# BTEMS.net
KiCad netlist of a schematic drawn in EAGLE
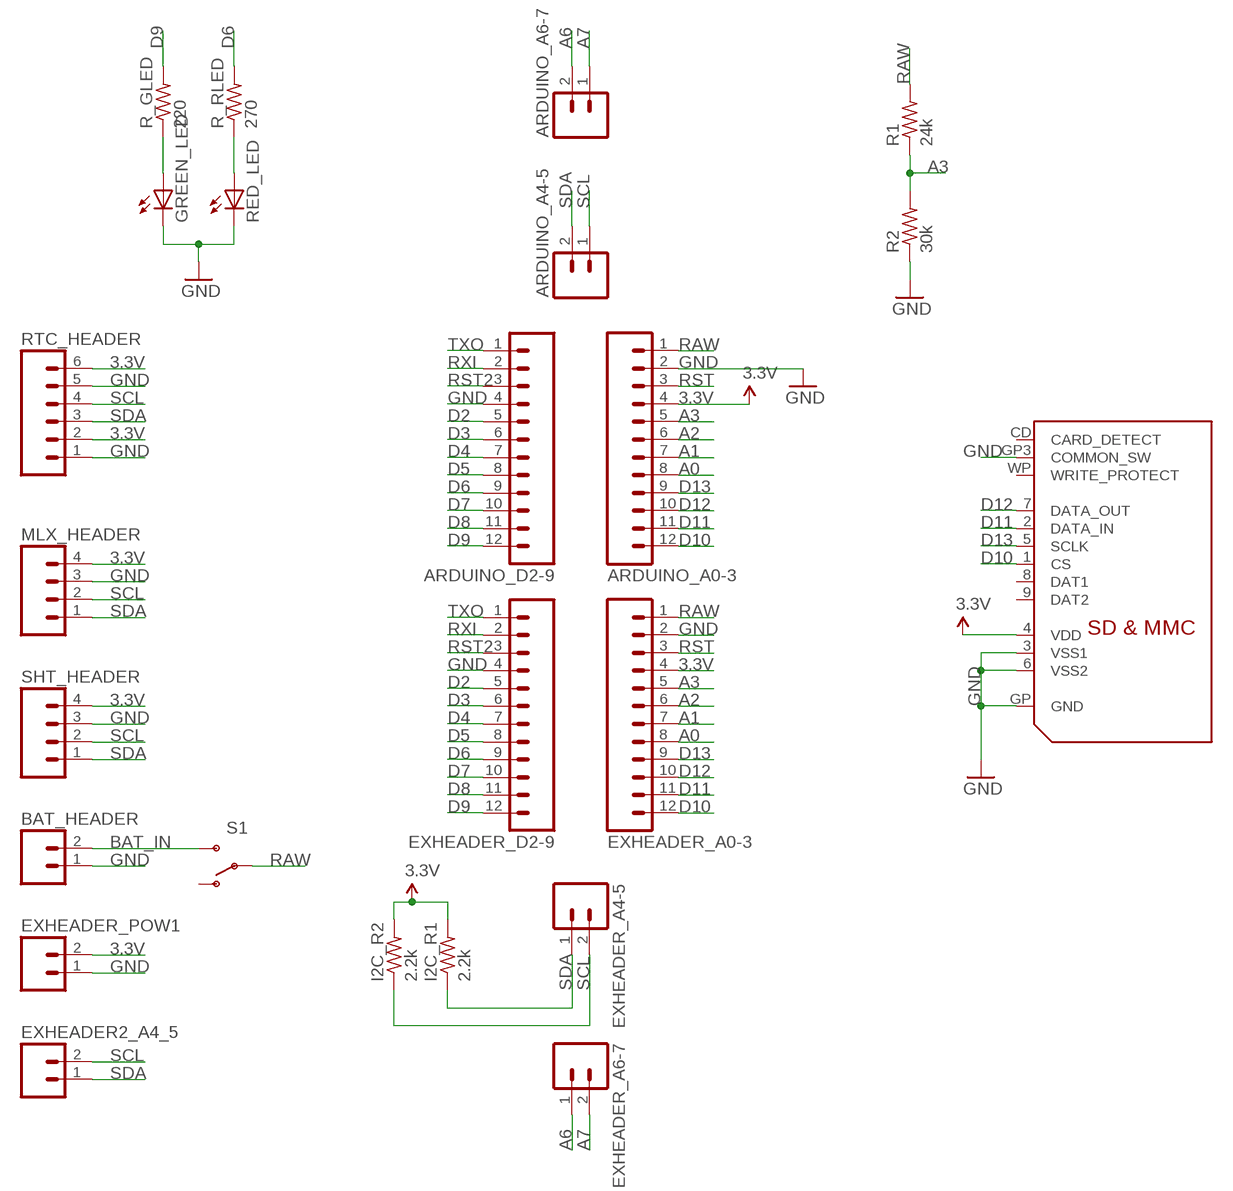
[diagram p0: schematic, sheet 1]

(export (version "E")
  (design (tool "Eeschema 10.0.6"))
  (components
    (comp (ref "ARDUINO_A0-3")
      (value "M12LOCK")
      (footprint "eagle-import:1X12_LOCK")
      (libsource (lib "eagle-import") (part "M12LOCK"))
    )
    (comp (ref "ARDUINO_A4-5")
      (value "M02PTH")
      (footprint "eagle-import:1X02")
      (libsource (lib "eagle-import") (part "M02PTH"))
    )
    (comp (ref "ARDUINO_A6-7")
      (value "M02PTH")
      (footprint "eagle-import:1X02")
      (libsource (lib "eagle-import") (part "M02PTH"))
    )
    (comp (ref "ARDUINO_D2-9")
      (value "M12LOCK")
      (footprint "eagle-import:1X12_LOCK")
      (libsource (lib "eagle-import") (part "M12LOCK"))
    )
    (comp (ref "BAT_HEADER")
      (value "M023.5MM")
      (footprint "eagle-import:SCREWTERMINAL-3.5MM-2")
      (libsource (lib "eagle-import") (part "M023.5MM"))
    )
    (comp (ref "EXHEADER2_A4_5")
      (value "M02PTH")
      (footprint "eagle-import:1X02")
      (libsource (lib "eagle-import") (part "M02PTH"))
    )
    (comp (ref "EXHEADER_A0-3")
      (value "M12PTH")
      (footprint "eagle-import:1X12")
      (libsource (lib "eagle-import") (part "M12PTH"))
    )
    (comp (ref "EXHEADER_A4-5")
      (value "M02LOCK")
      (footprint "eagle-import:1X02_LOCK")
      (libsource (lib "eagle-import") (part "M02LOCK"))
    )
    (comp (ref "EXHEADER_A6-7")
      (value "M02LOCK")
      (footprint "eagle-import:1X02_LOCK")
      (libsource (lib "eagle-import") (part "M02LOCK"))
    )
    (comp (ref "EXHEADER_D2-9")
      (value "M12PTH")
      (footprint "eagle-import:1X12")
      (libsource (lib "eagle-import") (part "M12PTH"))
    )
    (comp (ref "EXHEADER_POW1")
      (value "M02PTH")
      (footprint "eagle-import:1X02")
      (libsource (lib "eagle-import") (part "M02PTH"))
    )
    (comp (ref "GREEN_LED")
      (value "LED3MM")
      (footprint "eagle-import:LED3MM")
      (libsource (lib "eagle-import") (part "LED3MM"))
    )
    (comp (ref "I2C_R1")
      (value "2.2k")
      (footprint "eagle-import:0207_7")
      (libsource (lib "eagle-import") (part "R-US_0207/7"))
    )
    (comp (ref "I2C_R2")
      (value "2.2k")
      (footprint "eagle-import:0207_7")
      (libsource (lib "eagle-import") (part "R-US_0207/7"))
    )
    (comp (ref "MLX_HEADER")
      (value "M04LOCK")
      (footprint "eagle-import:1X04_LOCK")
      (libsource (lib "eagle-import") (part "M04LOCK"))
    )
    (comp (ref "R1")
      (value "24k")
      (footprint "eagle-import:0207_7")
      (libsource (lib "eagle-import") (part "R-US_0207/7"))
    )
    (comp (ref "R2")
      (value "30k")
      (footprint "eagle-import:0207_7")
      (libsource (lib "eagle-import") (part "R-US_0207/7"))
    )
    (comp (ref "RED_LED")
      (value "LED3MM")
      (footprint "eagle-import:LED3MM")
      (libsource (lib "eagle-import") (part "LED3MM"))
    )
    (comp (ref "RTC_HEADER")
      (value "M06FEMALE_LOCK")
      (footprint "eagle-import:1X06_FEMALE_LOCK.010")
      (libsource (lib "eagle-import") (part "M06FEMALE_LOCK"))
    )
    (comp (ref "R_GLED")
      (value "220")
      (footprint "eagle-import:0207_7")
      (libsource (lib "eagle-import") (part "R-US_0207/7"))
    )
    (comp (ref "R_RLED")
      (value "270")
      (footprint "eagle-import:0207_7")
      (libsource (lib "eagle-import") (part "R-US_0207/7"))
    )
    (comp (ref "S1")
      (value "SWITCH-SPDTPTH")
      (footprint "eagle-import:SWITCH-SPDT")
      (libsource (lib "eagle-import") (part "SWITCH-SPDTPTH"))
    )
    (comp (ref "SDSLOT")
      (value "SDMMC06132")
      (footprint "eagle-import:06132")
      (libsource (lib "eagle-import") (part "SDMMC06132"))
    )
    (comp (ref "SHT_HEADER")
      (value "M04LOCK")
      (footprint "eagle-import:1X04_LOCK")
      (libsource (lib "eagle-import") (part "M04LOCK"))
    )
  )
  (nets
    (net (code "1") (name "/A0") (class "Default")
      (node (ref "ARDUINO_A0-3") (pin "8") (pinfunction "8_8") (pintype "passive"))
      (node (ref "EXHEADER_A0-3") (pin "8") (pinfunction "8_8") (pintype "passive"))
    )
    (net (code "2") (name "/A1") (class "Default")
      (node (ref "ARDUINO_A0-3") (pin "7") (pinfunction "7_7") (pintype "passive"))
      (node (ref "EXHEADER_A0-3") (pin "7") (pinfunction "7_7") (pintype "passive"))
    )
    (net (code "3") (name "/A2") (class "Default")
      (node (ref "ARDUINO_A0-3") (pin "6") (pinfunction "6_6") (pintype "passive"))
      (node (ref "EXHEADER_A0-3") (pin "6") (pinfunction "6_6") (pintype "passive"))
    )
    (net (code "4") (name "/A3") (class "Default")
      (node (ref "ARDUINO_A0-3") (pin "5") (pinfunction "5_5") (pintype "passive"))
      (node (ref "EXHEADER_A0-3") (pin "5") (pinfunction "5_5") (pintype "passive"))
      (node (ref "R1") (pin "1") (pinfunction "1_1") (pintype "passive"))
      (node (ref "R2") (pin "2") (pinfunction "2_2") (pintype "passive"))
    )
    (net (code "5") (name "/A6") (class "Default")
      (node (ref "ARDUINO_A6-7") (pin "2") (pinfunction "2_2") (pintype "passive"))
      (node (ref "EXHEADER_A6-7") (pin "1") (pinfunction "1_1") (pintype "passive"))
    )
    (net (code "6") (name "/A7") (class "Default")
      (node (ref "ARDUINO_A6-7") (pin "1") (pinfunction "1_1") (pintype "passive"))
      (node (ref "EXHEADER_A6-7") (pin "2") (pinfunction "2_2") (pintype "passive"))
    )
    (net (code "7") (name "/BAT_IN") (class "Default")
      (node (ref "BAT_HEADER") (pin "2") (pinfunction "2_2") (pintype "passive"))
      (node (ref "S1") (pin "3") (pinfunction "S_3") (pintype "passive"))
    )
    (net (code "8") (name "/D2") (class "Default")
      (node (ref "ARDUINO_D2-9") (pin "5") (pinfunction "5_5") (pintype "passive"))
      (node (ref "EXHEADER_D2-9") (pin "5") (pinfunction "5_5") (pintype "passive"))
    )
    (net (code "9") (name "/D3") (class "Default")
      (node (ref "ARDUINO_D2-9") (pin "6") (pinfunction "6_6") (pintype "passive"))
      (node (ref "EXHEADER_D2-9") (pin "6") (pinfunction "6_6") (pintype "passive"))
    )
    (net (code "10") (name "/D4") (class "Default")
      (node (ref "ARDUINO_D2-9") (pin "7") (pinfunction "7_7") (pintype "passive"))
      (node (ref "EXHEADER_D2-9") (pin "7") (pinfunction "7_7") (pintype "passive"))
    )
    (net (code "11") (name "/D5") (class "Default")
      (node (ref "ARDUINO_D2-9") (pin "8") (pinfunction "8_8") (pintype "passive"))
      (node (ref "EXHEADER_D2-9") (pin "8") (pinfunction "8_8") (pintype "passive"))
    )
    (net (code "12") (name "/D6") (class "Default")
      (node (ref "ARDUINO_D2-9") (pin "9") (pinfunction "9_9") (pintype "passive"))
      (node (ref "EXHEADER_D2-9") (pin "9") (pinfunction "9_9") (pintype "passive"))
      (node (ref "R_RLED") (pin "2") (pinfunction "2_2") (pintype "passive"))
    )
    (net (code "13") (name "/D7") (class "Default")
      (node (ref "ARDUINO_D2-9") (pin "10") (pinfunction "10_10") (pintype "passive"))
      (node (ref "EXHEADER_D2-9") (pin "10") (pinfunction "10_10") (pintype "passive"))
    )
    (net (code "14") (name "/D8") (class "Default")
      (node (ref "ARDUINO_D2-9") (pin "11") (pinfunction "11_11") (pintype "passive"))
      (node (ref "EXHEADER_D2-9") (pin "11") (pinfunction "11_11") (pintype "passive"))
    )
    (net (code "15") (name "/D9") (class "Default")
      (node (ref "ARDUINO_D2-9") (pin "12") (pinfunction "12_12") (pintype "passive"))
      (node (ref "EXHEADER_D2-9") (pin "12") (pinfunction "12_12") (pintype "passive"))
      (node (ref "R_GLED") (pin "2") (pinfunction "2_2") (pintype "passive"))
    )
    (net (code "16") (name "/D10") (class "Default")
      (node (ref "ARDUINO_A0-3") (pin "12") (pinfunction "12_12") (pintype "passive"))
      (node (ref "EXHEADER_A0-3") (pin "12") (pinfunction "12_12") (pintype "passive"))
      (node (ref "SDSLOT") (pin "1") (pinfunction "CS_1") (pintype "input"))
    )
    (net (code "17") (name "/D11") (class "Default")
      (node (ref "ARDUINO_A0-3") (pin "11") (pinfunction "11_11") (pintype "passive"))
      (node (ref "EXHEADER_A0-3") (pin "11") (pinfunction "11_11") (pintype "passive"))
      (node (ref "SDSLOT") (pin "2") (pinfunction "DATA_IN_2") (pintype "input"))
    )
    (net (code "18") (name "/D12") (class "Default")
      (node (ref "ARDUINO_A0-3") (pin "10") (pinfunction "10_10") (pintype "passive"))
      (node (ref "EXHEADER_A0-3") (pin "10") (pinfunction "10_10") (pintype "passive"))
      (node (ref "SDSLOT") (pin "7") (pinfunction "DATA_OUT_7") (pintype "output"))
    )
    (net (code "19") (name "/D13") (class "Default")
      (node (ref "ARDUINO_A0-3") (pin "9") (pinfunction "9_9") (pintype "passive"))
      (node (ref "EXHEADER_A0-3") (pin "9") (pinfunction "9_9") (pintype "passive"))
      (node (ref "SDSLOT") (pin "5") (pinfunction "SCLK_5") (pintype "input"))
    )
    (net (code "20") (name "/RAW") (class "Default")
      (node (ref "ARDUINO_A0-3") (pin "1") (pinfunction "1_1") (pintype "passive"))
      (node (ref "EXHEADER_A0-3") (pin "1") (pinfunction "1_1") (pintype "passive"))
      (node (ref "R1") (pin "2") (pinfunction "2_2") (pintype "passive"))
      (node (ref "S1") (pin "2") (pinfunction "P_2") (pintype "passive"))
    )
    (net (code "21") (name "/RST") (class "Default")
      (node (ref "ARDUINO_A0-3") (pin "3") (pinfunction "3_3") (pintype "passive"))
      (node (ref "EXHEADER_A0-3") (pin "3") (pinfunction "3_3") (pintype "passive"))
    )
    (net (code "22") (name "/RST2") (class "Default")
      (node (ref "ARDUINO_D2-9") (pin "3") (pinfunction "3_3") (pintype "passive"))
      (node (ref "EXHEADER_D2-9") (pin "3") (pinfunction "3_3") (pintype "passive"))
    )
    (net (code "23") (name "/RXI") (class "Default")
      (node (ref "ARDUINO_D2-9") (pin "2") (pinfunction "2_2") (pintype "passive"))
      (node (ref "EXHEADER_D2-9") (pin "2") (pinfunction "2_2") (pintype "passive"))
    )
    (net (code "24") (name "/SCL") (class "Default")
      (node (ref "ARDUINO_A4-5") (pin "1") (pinfunction "1_1") (pintype "passive"))
      (node (ref "EXHEADER2_A4_5") (pin "2") (pinfunction "2_2") (pintype "passive"))
      (node (ref "EXHEADER_A4-5") (pin "2") (pinfunction "2_2") (pintype "passive"))
      (node (ref "I2C_R2") (pin "1") (pinfunction "1_1") (pintype "passive"))
      (node (ref "MLX_HEADER") (pin "2") (pinfunction "2_2") (pintype "passive"))
      (node (ref "RTC_HEADER") (pin "4") (pinfunction "4_4") (pintype "passive"))
      (node (ref "SHT_HEADER") (pin "2") (pinfunction "2_2") (pintype "passive"))
    )
    (net (code "25") (name "/SDA") (class "Default")
      (node (ref "ARDUINO_A4-5") (pin "2") (pinfunction "2_2") (pintype "passive"))
      (node (ref "EXHEADER2_A4_5") (pin "1") (pinfunction "1_1") (pintype "passive"))
      (node (ref "EXHEADER_A4-5") (pin "1") (pinfunction "1_1") (pintype "passive"))
      (node (ref "I2C_R1") (pin "1") (pinfunction "1_1") (pintype "passive"))
      (node (ref "MLX_HEADER") (pin "1") (pinfunction "1_1") (pintype "passive"))
      (node (ref "RTC_HEADER") (pin "3") (pinfunction "3_3") (pintype "passive"))
      (node (ref "SHT_HEADER") (pin "1") (pinfunction "1_1") (pintype "passive"))
    )
    (net (code "26") (name "/TXO") (class "Default")
      (node (ref "ARDUINO_D2-9") (pin "1") (pinfunction "1_1") (pintype "passive"))
      (node (ref "EXHEADER_D2-9") (pin "1") (pinfunction "1_1") (pintype "passive"))
    )
    (net (code "27") (name "3.3V") (class "Default")
      (node (ref "ARDUINO_A0-3") (pin "4") (pinfunction "4_4") (pintype "passive"))
      (node (ref "EXHEADER_A0-3") (pin "4") (pinfunction "4_4") (pintype "passive"))
      (node (ref "EXHEADER_POW1") (pin "2") (pinfunction "2_2") (pintype "passive"))
      (node (ref "I2C_R1") (pin "2") (pinfunction "2_2") (pintype "passive"))
      (node (ref "I2C_R2") (pin "2") (pinfunction "2_2") (pintype "passive"))
      (node (ref "MLX_HEADER") (pin "4") (pinfunction "4_4") (pintype "passive"))
      (node (ref "RTC_HEADER") (pin "2") (pinfunction "2_2") (pintype "passive"))
      (node (ref "RTC_HEADER") (pin "6") (pinfunction "6_6") (pintype "passive"))
      (node (ref "SDSLOT") (pin "4") (pinfunction "VDD_4") (pintype "power_in"))
      (node (ref "SHT_HEADER") (pin "4") (pinfunction "4_4") (pintype "passive"))
    )
    (net (code "28") (name "GND") (class "Default")
      (node (ref "ARDUINO_A0-3") (pin "2") (pinfunction "2_2") (pintype "passive"))
      (node (ref "ARDUINO_D2-9") (pin "4") (pinfunction "4_4") (pintype "passive"))
      (node (ref "BAT_HEADER") (pin "1") (pinfunction "1_1") (pintype "passive"))
      (node (ref "EXHEADER_A0-3") (pin "2") (pinfunction "2_2") (pintype "passive"))
      (node (ref "EXHEADER_D2-9") (pin "4") (pinfunction "4_4") (pintype "passive"))
      (node (ref "EXHEADER_POW1") (pin "1") (pinfunction "1_1") (pintype "passive"))
      (node (ref "GREEN_LED") (pin "K") (pinfunction "C_K") (pintype "passive"))
      (node (ref "MLX_HEADER") (pin "3") (pinfunction "3_3") (pintype "passive"))
      (node (ref "R2") (pin "1") (pinfunction "1_1") (pintype "passive"))
      (node (ref "RED_LED") (pin "K") (pinfunction "C_K") (pintype "passive"))
      (node (ref "RTC_HEADER") (pin "1") (pinfunction "1_1") (pintype "passive"))
      (node (ref "RTC_HEADER") (pin "5") (pinfunction "5_5") (pintype "passive"))
      (node (ref "SDSLOT") (pin "3") (pinfunction "VSS1_3") (pintype "power_in"))
      (node (ref "SDSLOT") (pin "6") (pinfunction "VSS2_6") (pintype "power_in"))
      (node (ref "SDSLOT") (pin "GP") (pinfunction "GND_GP") (pintype "power_in"))
      (node (ref "SDSLOT") (pin "GP3") (pinfunction "COMMON_SW_GP3") (pintype "passive"))
      (node (ref "SHT_HEADER") (pin "3") (pinfunction "3_3") (pintype "passive"))
    )
    (net (code "29") (name "Net-(GREEN_LED-PadA)") (class "Default")
      (node (ref "GREEN_LED") (pin "A") (pinfunction "A_A") (pintype "passive"))
      (node (ref "R_GLED") (pin "1") (pinfunction "1_1") (pintype "passive"))
    )
    (net (code "30") (name "Net-(RED_LED-PadA)") (class "Default")
      (node (ref "RED_LED") (pin "A") (pinfunction "A_A") (pintype "passive"))
      (node (ref "R_RLED") (pin "1") (pinfunction "1_1") (pintype "passive"))
    )
    (net (code "31") (name "unconnected-(S1-O-Pad1)") (class "Default")
      (node (ref "S1") (pin "1") (pinfunction "O_1") (pintype "passive"))
    )
    (net (code "32") (name "unconnected-(SDSLOT-CARD_DETECT-PadCD)") (class "Default")
      (node (ref "SDSLOT") (pin "CD") (pinfunction "CARD_DETECT_CD") (pintype "passive"))
    )
    (net (code "33") (name "unconnected-(SDSLOT-DAT1-Pad8)") (class "Default")
      (node (ref "SDSLOT") (pin "8") (pinfunction "DAT1_8") (pintype "bidirectional"))
    )
    (net (code "34") (name "unconnected-(SDSLOT-DAT2-Pad9)") (class "Default")
      (node (ref "SDSLOT") (pin "9") (pinfunction "DAT2_9") (pintype "bidirectional"))
    )
    (net (code "35") (name "unconnected-(SDSLOT-WRITE_PROTECT-PadWP)") (class "Default")
      (node (ref "SDSLOT") (pin "WP") (pinfunction "WRITE_PROTECT_WP") (pintype "passive"))
    )
  )
)
